# pca10040_sheet3_buttons_and_leds.net
KiCad netlist of a schematic drawn in Altium Designer
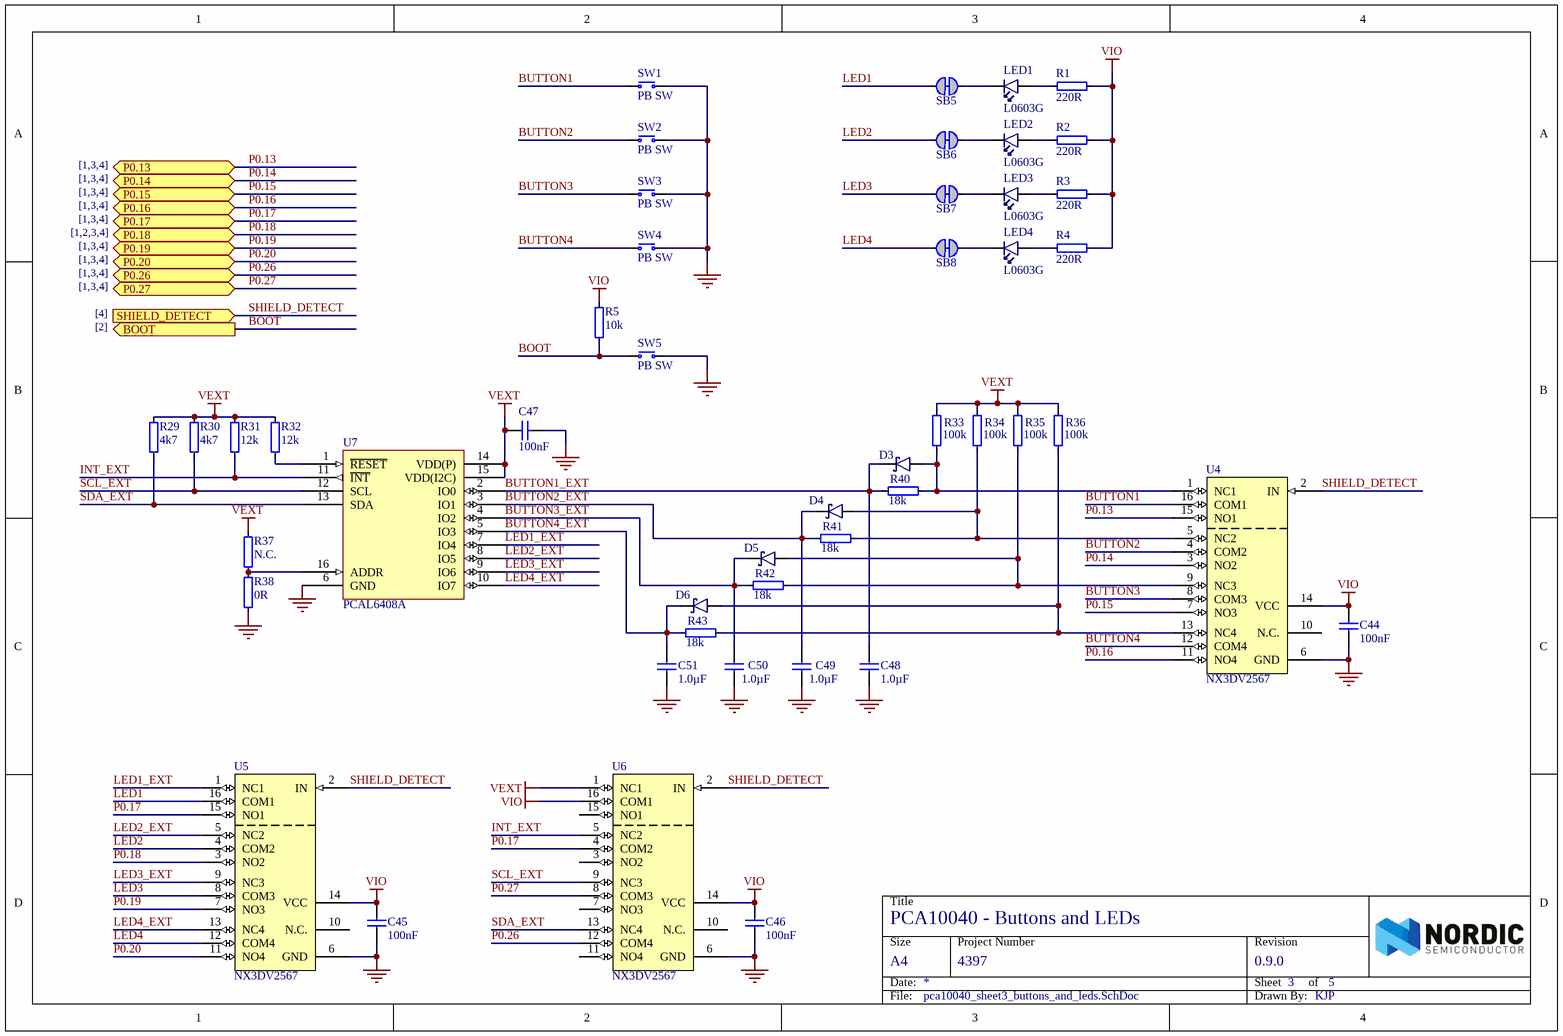
[diagram p0: pca10040_sheet3_buttons_and_leds.SchDoc]

(export (version "E")
  (design (tool "Eeschema 10.0.6"))
  (components
    (comp (ref "C44")
      (value "100nF")
      (footprint "CAPC1005X04L")
      (description "Capacitor, X7R, ±10%")
      (fields (field (name "PART NUMBER") "C0402-100n") (field (name "PUBLISHER") "Nordic Semiconductor"))
      (libsource (lib "Nordic Passive DB") (part "CAP"))
    )
    (comp (ref "C45")
      (value "100nF")
      (footprint "CAPC1005X04L")
      (description "Capacitor, X7R, ±10%")
      (fields (field (name "PART NUMBER") "C0402-100n") (field (name "PUBLISHER") "Nordic Semiconductor"))
      (libsource (lib "Nordic Passive DB") (part "CAP"))
    )
    (comp (ref "C46")
      (value "100nF")
      (footprint "CAPC1005X04L")
      (description "Capacitor, X7R, ±10%")
      (fields (field (name "PART NUMBER") "C0402-100n") (field (name "PUBLISHER") "Nordic Semiconductor"))
      (libsource (lib "Nordic Passive DB") (part "CAP"))
    )
    (comp (ref "C47")
      (value "100nF")
      (footprint "CAPC1005X04L")
      (description "Capacitor, X7R, ±10%")
      (fields (field (name "PART NUMBER") "C0402-100n") (field (name "PUBLISHER") "Nordic Semiconductor"))
      (libsource (lib "Nordic Passive DB") (part "CAP"))
    )
    (comp (ref "C48")
      (value "1.0µF")
      (footprint "CAPC1005X04L")
      (description "Capacitor, X5R, ±5%")
      (fields (field (name "PART NUMBER") "C0402-1µ0") (field (name "PUBLISHER") "Nordic Semiconductor"))
      (libsource (lib "Nordic Passive DB") (part "CAP"))
    )
    (comp (ref "C49")
      (value "1.0µF")
      (footprint "CAPC1005X04L")
      (description "Capacitor, X5R, ±5%")
      (fields (field (name "PART NUMBER") "C0402-1µ0") (field (name "PUBLISHER") "Nordic Semiconductor"))
      (libsource (lib "Nordic Passive DB") (part "CAP"))
    )
    (comp (ref "C50")
      (value "1.0µF")
      (footprint "CAPC1005X04L")
      (description "Capacitor, X5R, ±5%")
      (fields (field (name "PART NUMBER") "C0402-1µ0") (field (name "PUBLISHER") "Nordic Semiconductor"))
      (libsource (lib "Nordic Passive DB") (part "CAP"))
    )
    (comp (ref "C51")
      (value "1.0µF")
      (footprint "CAPC1005X04L")
      (description "Capacitor, X5R, ±5%")
      (fields (field (name "PART NUMBER") "C0402-1µ0") (field (name "PUBLISHER") "Nordic Semiconductor"))
      (libsource (lib "Nordic Passive DB") (part "CAP"))
    )
    (comp (ref "D3")
      (value "1PS79SB30.115")
      (footprint "SOD-523")
      (description "Diode Schottky Vf=0.38, Vr=40V, If=200mA, Ir=500nA")
      (fields (field (name "MANUFACTURER") "NXP") (field (name "PUBLISHER") "Nordic Semiconductor"))
      (libsource (lib "Nordic Discrete DB") (part "D{colon}SCHOTTKY"))
    )
    (comp (ref "D4")
      (value "1PS79SB30.115")
      (footprint "SOD-523")
      (description "Diode Schottky Vf=0.38, Vr=40V, If=200mA, Ir=500nA")
      (fields (field (name "MANUFACTURER") "NXP") (field (name "PUBLISHER") "Nordic Semiconductor"))
      (libsource (lib "Nordic Discrete DB") (part "D{colon}SCHOTTKY"))
    )
    (comp (ref "D5")
      (value "1PS79SB30.115")
      (footprint "SOD-523")
      (description "Diode Schottky Vf=0.38, Vr=40V, If=200mA, Ir=500nA")
      (fields (field (name "MANUFACTURER") "NXP") (field (name "PUBLISHER") "Nordic Semiconductor"))
      (libsource (lib "Nordic Discrete DB") (part "D{colon}SCHOTTKY"))
    )
    (comp (ref "D6")
      (value "1PS79SB30.115")
      (footprint "SOD-523")
      (description "Diode Schottky Vf=0.38, Vr=40V, If=200mA, Ir=500nA")
      (fields (field (name "MANUFACTURER") "NXP") (field (name "PUBLISHER") "Nordic Semiconductor"))
      (libsource (lib "Nordic Discrete DB") (part "D{colon}SCHOTTKY"))
    )
    (comp (ref "LED1")
      (value "L0603G")
      (footprint "LED_0603_G")
      (description "LED 0603, EL19-21SYGC")
      (fields
        (field (name "PART NUMBER") "EL19-21SYGC")
        (field (name "MANUFACTURER") "Everlight")
        (field (name "PUBLISHER") "Nordic Semiconductor")
      )
      (libsource (lib "Nordic Discrete DB") (part "D{colon}LED"))
    )
    (comp (ref "LED2")
      (value "L0603G")
      (footprint "LED_0603_G")
      (description "LED 0603, EL19-21SYGC")
      (fields
        (field (name "PART NUMBER") "EL19-21SYGC")
        (field (name "MANUFACTURER") "Everlight")
        (field (name "PUBLISHER") "Nordic Semiconductor")
      )
      (libsource (lib "Nordic Discrete DB") (part "D{colon}LED"))
    )
    (comp (ref "LED3")
      (value "L0603G")
      (footprint "LED_0603_G")
      (description "LED 0603, EL19-21SYGC")
      (fields
        (field (name "PART NUMBER") "EL19-21SYGC")
        (field (name "MANUFACTURER") "Everlight")
        (field (name "PUBLISHER") "Nordic Semiconductor")
      )
      (libsource (lib "Nordic Discrete DB") (part "D{colon}LED"))
    )
    (comp (ref "LED4")
      (value "L0603G")
      (footprint "LED_0603_G")
      (description "LED 0603, EL19-21SYGC")
      (fields
        (field (name "PART NUMBER") "EL19-21SYGC")
        (field (name "MANUFACTURER") "Everlight")
        (field (name "PUBLISHER") "Nordic Semiconductor")
      )
      (libsource (lib "Nordic Discrete DB") (part "D{colon}LED"))
    )
    (comp (ref "R1")
      (value "220R")
      (footprint "RESC1005X04L")
      (description "Resistor, ±1%, 0.063W")
      (fields (field (name "PART NUMBER") "R0402-220") (field (name "PUBLISHER") "Nordic Semiconductor"))
      (libsource (lib "Nordic Passive DB") (part "RES_1"))
    )
    (comp (ref "R2")
      (value "220R")
      (footprint "RESC1005X04L")
      (description "Resistor, ±1%, 0.063W")
      (fields (field (name "PART NUMBER") "R0402-220") (field (name "PUBLISHER") "Nordic Semiconductor"))
      (libsource (lib "Nordic Passive DB") (part "RES_1"))
    )
    (comp (ref "R3")
      (value "220R")
      (footprint "RESC1005X04L")
      (description "Resistor, ±1%, 0.063W")
      (fields (field (name "PART NUMBER") "R0402-220") (field (name "PUBLISHER") "Nordic Semiconductor"))
      (libsource (lib "Nordic Passive DB") (part "RES_1"))
    )
    (comp (ref "R4")
      (value "220R")
      (footprint "RESC1005X04L")
      (description "Resistor, ±1%, 0.063W")
      (fields (field (name "PART NUMBER") "R0402-220") (field (name "PUBLISHER") "Nordic Semiconductor"))
      (libsource (lib "Nordic Passive DB") (part "RES_1"))
    )
    (comp (ref "R5")
      (value "10k")
      (footprint "RESC1005X04L")
      (description "Resistor, ±1%, 0.063W")
      (fields (field (name "PART NUMBER") "R0402-10k") (field (name "PUBLISHER") "Nordic Semiconductor"))
      (libsource (lib "Nordic Passive DB") (part "RES_1"))
    )
    (comp (ref "R29")
      (value "4k7")
      (footprint "RESC1005X04L")
      (description "Resistor, ±1%, 0.063W")
      (fields (field (name "PART NUMBER") "R0402-4k7") (field (name "PUBLISHER") "Nordic Semiconductor"))
      (libsource (lib "Nordic Passive DB") (part "RES_1"))
    )
    (comp (ref "R30")
      (value "4k7")
      (footprint "RESC1005X04L")
      (description "Resistor, ±1%, 0.063W")
      (fields (field (name "PART NUMBER") "R0402-4k7") (field (name "PUBLISHER") "Nordic Semiconductor"))
      (libsource (lib "Nordic Passive DB") (part "RES_1"))
    )
    (comp (ref "R31")
      (value "12k")
      (footprint "RESC1005X04L")
      (description "Resistor, ±1%, 0.063W")
      (fields (field (name "PART NUMBER") "R0402-12k") (field (name "PUBLISHER") "Nordic Semiconductor"))
      (libsource (lib "Nordic Passive DB") (part "RES_1"))
    )
    (comp (ref "R32")
      (value "12k")
      (footprint "RESC1005X04L")
      (description "Resistor, ±1%, 0.063W")
      (fields (field (name "PART NUMBER") "R0402-12k") (field (name "PUBLISHER") "Nordic Semiconductor"))
      (libsource (lib "Nordic Passive DB") (part "RES_1"))
    )
    (comp (ref "R33")
      (value "100k")
      (footprint "RESC1005X04L")
      (description "Resistor, ±1%, 0.063W")
      (fields (field (name "PART NUMBER") "R0402-100k") (field (name "PUBLISHER") "Nordic Semiconductor"))
      (libsource (lib "Nordic Passive DB") (part "RES_1"))
    )
    (comp (ref "R34")
      (value "100k")
      (footprint "RESC1005X04L")
      (description "Resistor, ±1%, 0.063W")
      (fields (field (name "PART NUMBER") "R0402-100k") (field (name "PUBLISHER") "Nordic Semiconductor"))
      (libsource (lib "Nordic Passive DB") (part "RES_1"))
    )
    (comp (ref "R35")
      (value "100k")
      (footprint "RESC1005X04L")
      (description "Resistor, ±1%, 0.063W")
      (fields (field (name "PART NUMBER") "R0402-100k") (field (name "PUBLISHER") "Nordic Semiconductor"))
      (libsource (lib "Nordic Passive DB") (part "RES_1"))
    )
    (comp (ref "R36")
      (value "100k")
      (footprint "RESC1005X04L")
      (description "Resistor, ±1%, 0.063W")
      (fields (field (name "PART NUMBER") "R0402-100k") (field (name "PUBLISHER") "Nordic Semiconductor"))
      (libsource (lib "Nordic Passive DB") (part "RES_1"))
    )
    (comp (ref "R37")
      (value "N.C.")
      (footprint "RESC1005X04L")
      (description "Not mounted")
      (fields (field (name "PART NUMBER") "R0402-N.C.") (field (name "PUBLISHER") "Nordic Semiconductor"))
      (libsource (lib "Nordic Passive DB") (part "RES_1"))
    )
    (comp (ref "R38")
      (value "0R")
      (footprint "RESC1005X04L")
      (description "Resistor, ±5%, 0.063W")
      (fields (field (name "PART NUMBER") "R0402-0R") (field (name "PUBLISHER") "Nordic Semiconductor"))
      (libsource (lib "Nordic Passive DB") (part "RES_1"))
    )
    (comp (ref "R40")
      (value "18k")
      (footprint "RESC1005X04L")
      (description "Resistor, ±1%, 0.063W")
      (fields (field (name "PART NUMBER") "R0402-18k") (field (name "PUBLISHER") "Nordic Semiconductor"))
      (libsource (lib "Nordic Passive DB") (part "RES_1"))
    )
    (comp (ref "R41")
      (value "18k")
      (footprint "RESC1005X04L")
      (description "Resistor, ±1%, 0.063W")
      (fields (field (name "PART NUMBER") "R0402-18k") (field (name "PUBLISHER") "Nordic Semiconductor"))
      (libsource (lib "Nordic Passive DB") (part "RES_1"))
    )
    (comp (ref "R42")
      (value "18k")
      (footprint "RESC1005X04L")
      (description "Resistor, ±1%, 0.063W")
      (fields (field (name "PART NUMBER") "R0402-18k") (field (name "PUBLISHER") "Nordic Semiconductor"))
      (libsource (lib "Nordic Passive DB") (part "RES_1"))
    )
    (comp (ref "R43")
      (value "18k")
      (footprint "RESC1005X04L")
      (description "Resistor, ±1%, 0.063W")
      (fields (field (name "PART NUMBER") "R0402-18k") (field (name "PUBLISHER") "Nordic Semiconductor"))
      (libsource (lib "Nordic Passive DB") (part "RES_1"))
    )
    (comp (ref "SB5")
      (value "Solderbridge")
      (footprint "Solderbridge_Shorted")
      (description "Shorted Solderbridge")
      (fields
        (field (name "PART NUMBER") "Solderbridge Shorted")
        (field (name "PUBLISHER") "Nordic Semiconductor")
      )
      (libsource (lib "Nordic Passive DB") (part "SOLDERBRIDGE_SHORTED"))
    )
    (comp (ref "SB6")
      (value "Solderbridge")
      (footprint "Solderbridge_Shorted")
      (description "Shorted Solderbridge")
      (fields
        (field (name "PART NUMBER") "Solderbridge Shorted")
        (field (name "PUBLISHER") "Nordic Semiconductor")
      )
      (libsource (lib "Nordic Passive DB") (part "SOLDERBRIDGE_SHORTED"))
    )
    (comp (ref "SB7")
      (value "Solderbridge")
      (footprint "Solderbridge_Shorted")
      (description "Shorted Solderbridge")
      (fields
        (field (name "PART NUMBER") "Solderbridge Shorted")
        (field (name "PUBLISHER") "Nordic Semiconductor")
      )
      (libsource (lib "Nordic Passive DB") (part "SOLDERBRIDGE_SHORTED"))
    )
    (comp (ref "SB8")
      (value "Solderbridge")
      (footprint "Solderbridge_Shorted")
      (description "Shorted Solderbridge")
      (fields
        (field (name "PART NUMBER") "Solderbridge Shorted")
        (field (name "PUBLISHER") "Nordic Semiconductor")
      )
      (libsource (lib "Nordic Passive DB") (part "SOLDERBRIDGE_SHORTED"))
    )
    (comp (ref "SW1")
      (value "PB SW")
      (footprint "ALPS_SKHUxxx010_WO_GND")
      (description "ALPS - SKHUALE010 - Tactile Switch, SPNO, SMD, 6.5x6.2x2.5mm")
      (fields
        (field (name "PART NUMBER") "ALPS_SKHUALE010")
        (field (name "MANUFACTURER") "Alps")
        (field (name "PUBLISHER") "Nordic Semiconductor")
      )
      (libsource (lib "Nordic Discrete DB") (part "SW-PB"))
    )
    (comp (ref "SW2")
      (value "PB SW")
      (footprint "ALPS_SKHUxxx010_WO_GND")
      (description "ALPS - SKHUALE010 - Tactile Switch, SPNO, SMD, 6.5x6.2x2.5mm")
      (fields
        (field (name "PART NUMBER") "ALPS_SKHUALE010")
        (field (name "MANUFACTURER") "Alps")
        (field (name "PUBLISHER") "Nordic Semiconductor")
      )
      (libsource (lib "Nordic Discrete DB") (part "SW-PB"))
    )
    (comp (ref "SW3")
      (value "PB SW")
      (footprint "ALPS_SKHUxxx010_WO_GND")
      (description "ALPS - SKHUALE010 - Tactile Switch, SPNO, SMD, 6.5x6.2x2.5mm")
      (fields
        (field (name "PART NUMBER") "ALPS_SKHUALE010")
        (field (name "MANUFACTURER") "Alps")
        (field (name "PUBLISHER") "Nordic Semiconductor")
      )
      (libsource (lib "Nordic Discrete DB") (part "SW-PB"))
    )
    (comp (ref "SW4")
      (value "PB SW")
      (footprint "ALPS_SKHUxxx010_WO_GND")
      (description "ALPS - SKHUALE010 - Tactile Switch, SPNO, SMD, 6.5x6.2x2.5mm")
      (fields
        (field (name "PART NUMBER") "ALPS_SKHUALE010")
        (field (name "MANUFACTURER") "Alps")
        (field (name "PUBLISHER") "Nordic Semiconductor")
      )
      (libsource (lib "Nordic Discrete DB") (part "SW-PB"))
    )
    (comp (ref "SW5")
      (value "PB SW")
      (footprint "ALPS_SKHUxxx010_WO_GND")
      (description "ALPS - SKHUALE010 - Tactile Switch, SPNO, SMD, 6.5x6.2x2.5mm")
      (fields
        (field (name "PART NUMBER") "ALPS_SKHUALE010")
        (field (name "MANUFACTURER") "Alps")
        (field (name "PUBLISHER") "Nordic Semiconductor")
      )
      (libsource (lib "Nordic Discrete DB") (part "SW-PB"))
    )
    (comp (ref "U4")
      (value "NX3DV2567")
      (footprint "XQFN40P180X260X50-16N")
      (description "Low-ohmic four-pole double-throw analog switch")
      (fields
        (field (name "PART NUMBER") "NX3DV2567GU")
        (field (name "MANUFACTURER") "NXP Semiconductors")
        (field (name "PUBLISHER") "Nordic Semiconductor")
      )
      (libsource (lib "Nordic Active DB") (part "NX3DV2567"))
    )
    (comp (ref "U5")
      (value "NX3DV2567")
      (footprint "XQFN40P180X260X50-16N")
      (description "Low-ohmic four-pole double-throw analog switch")
      (fields
        (field (name "PART NUMBER") "NX3DV2567GU")
        (field (name "MANUFACTURER") "NXP Semiconductors")
        (field (name "PUBLISHER") "Nordic Semiconductor")
      )
      (libsource (lib "Nordic Active DB") (part "NX3DV2567"))
    )
    (comp (ref "U6")
      (value "NX3DV2567")
      (footprint "XQFN40P180X260X50-16N")
      (description "Low-ohmic four-pole double-throw analog switch")
      (fields
        (field (name "PART NUMBER") "NX3DV2567GU")
        (field (name "MANUFACTURER") "NXP Semiconductors")
        (field (name "PUBLISHER") "Nordic Semiconductor")
      )
      (libsource (lib "Nordic Active DB") (part "NX3DV2567"))
    )
    (comp (ref "U7")
      (value "PCAL6408A")
      (footprint "XQFN40P180X260X50-16N")
      (description "8-bit I2C-bus I/O expander with interrupt output")
      (fields
        (field (name "PART NUMBER") "PCAL6408AHK")
        (field (name "MANUFACTURER") "NXP Semiconductors")
        (field (name "PUBLISHER") "Nordic Semiconductor")
      )
      (libsource (lib "Nordic Active DB") (part "PCAL6408AHK"))
    )
  )
  (nets
    (net (code "1") (name "/BOOT") (class "Default")
      (node (ref "R5") (pin "1") (pinfunction "1_1") (pintype "passive"))
      (node (ref "SW5") (pin "1") (pinfunction "N.O_1") (pintype "passive"))
    )
    (net (code "2") (name "/BUTTON1") (class "Default")
      (node (ref "SW1") (pin "1") (pinfunction "N.O_1") (pintype "passive"))
      (node (ref "U4") (pin "16") (pinfunction "COM1_16") (pintype "bidirectional"))
    )
    (net (code "3") (name "/BUTTON1_EXT") (class "Default")
      (node (ref "C48") (pin "1") (pinfunction "1_1") (pintype "passive"))
      (node (ref "D3") (pin "3") (pinfunction "C_3") (pintype "passive"))
      (node (ref "R40") (pin "1") (pinfunction "1_1") (pintype "passive"))
      (node (ref "U7") (pin "2") (pinfunction "IO0_2") (pintype "bidirectional"))
    )
    (net (code "4") (name "/BUTTON2") (class "Default")
      (node (ref "SW2") (pin "1") (pinfunction "N.O_1") (pintype "passive"))
      (node (ref "U4") (pin "4") (pinfunction "COM2_4") (pintype "bidirectional"))
    )
    (net (code "5") (name "/BUTTON2_EXT") (class "Default")
      (node (ref "C49") (pin "2") (pinfunction "2_2") (pintype "passive"))
      (node (ref "D4") (pin "3") (pinfunction "C_3") (pintype "passive"))
      (node (ref "R41") (pin "1") (pinfunction "1_1") (pintype "passive"))
      (node (ref "U7") (pin "3") (pinfunction "IO1_3") (pintype "bidirectional"))
    )
    (net (code "6") (name "/BUTTON3") (class "Default")
      (node (ref "SW3") (pin "1") (pinfunction "N.O_1") (pintype "passive"))
      (node (ref "U4") (pin "8") (pinfunction "COM3_8") (pintype "bidirectional"))
    )
    (net (code "7") (name "/BUTTON3_EXT") (class "Default")
      (node (ref "C50") (pin "2") (pinfunction "2_2") (pintype "passive"))
      (node (ref "D5") (pin "3") (pinfunction "C_3") (pintype "passive"))
      (node (ref "R42") (pin "1") (pinfunction "1_1") (pintype "passive"))
      (node (ref "U7") (pin "4") (pinfunction "IO2_4") (pintype "bidirectional"))
    )
    (net (code "8") (name "/BUTTON4") (class "Default")
      (node (ref "SW4") (pin "1") (pinfunction "N.O_1") (pintype "passive"))
      (node (ref "U4") (pin "12") (pinfunction "COM4_12") (pintype "bidirectional"))
    )
    (net (code "9") (name "/BUTTON4_EXT") (class "Default")
      (node (ref "C51") (pin "1") (pinfunction "1_1") (pintype "passive"))
      (node (ref "D6") (pin "3") (pinfunction "C_3") (pintype "passive"))
      (node (ref "R43") (pin "1") (pinfunction "1_1") (pintype "passive"))
      (node (ref "U7") (pin "5") (pinfunction "IO3_5") (pintype "bidirectional"))
    )
    (net (code "10") (name "/INT_EXT") (class "Default")
      (node (ref "R31") (pin "1") (pinfunction "1_1") (pintype "passive"))
      (node (ref "U6") (pin "5") (pinfunction "NC2_5") (pintype "bidirectional"))
      (node (ref "U7") (pin "11") (pinfunction "~{INT}_11") (pintype "output"))
    )
    (net (code "11") (name "/LED1") (class "Default")
      (node (ref "SB5") (pin "1") (pinfunction "0_1") (pintype "passive"))
      (node (ref "U5") (pin "16") (pinfunction "COM1_16") (pintype "bidirectional"))
    )
    (net (code "12") (name "/LED1_EXT") (class "Default")
      (node (ref "U5") (pin "1") (pinfunction "NC1_1") (pintype "bidirectional"))
      (node (ref "U7") (pin "7") (pinfunction "IO4_7") (pintype "bidirectional"))
    )
    (net (code "13") (name "/LED2") (class "Default")
      (node (ref "SB6") (pin "1") (pinfunction "0_1") (pintype "passive"))
      (node (ref "U5") (pin "4") (pinfunction "COM2_4") (pintype "bidirectional"))
    )
    (net (code "14") (name "/LED2_EXT") (class "Default")
      (node (ref "U5") (pin "5") (pinfunction "NC2_5") (pintype "bidirectional"))
      (node (ref "U7") (pin "8") (pinfunction "IO5_8") (pintype "bidirectional"))
    )
    (net (code "15") (name "/LED3") (class "Default")
      (node (ref "SB7") (pin "1") (pinfunction "0_1") (pintype "passive"))
      (node (ref "U5") (pin "8") (pinfunction "COM3_8") (pintype "bidirectional"))
    )
    (net (code "16") (name "/LED3_EXT") (class "Default")
      (node (ref "U5") (pin "9") (pinfunction "NC3_9") (pintype "bidirectional"))
      (node (ref "U7") (pin "9") (pinfunction "IO6_9") (pintype "bidirectional"))
    )
    (net (code "17") (name "/LED4") (class "Default")
      (node (ref "SB8") (pin "1") (pinfunction "0_1") (pintype "passive"))
      (node (ref "U5") (pin "12") (pinfunction "COM4_12") (pintype "bidirectional"))
    )
    (net (code "18") (name "/LED4_EXT") (class "Default")
      (node (ref "U5") (pin "13") (pinfunction "NC4_13") (pintype "bidirectional"))
      (node (ref "U7") (pin "10") (pinfunction "IO7_10") (pintype "bidirectional"))
    )
    (net (code "19") (name "/P0.13") (class "Default")
      (node (ref "U4") (pin "15") (pinfunction "NO1_15") (pintype "bidirectional"))
    )
    (net (code "20") (name "/P0.14") (class "Default")
      (node (ref "U4") (pin "3") (pinfunction "NO2_3") (pintype "bidirectional"))
    )
    (net (code "21") (name "/P0.15") (class "Default")
      (node (ref "U4") (pin "7") (pinfunction "NO3_7") (pintype "bidirectional"))
    )
    (net (code "22") (name "/P0.16") (class "Default")
      (node (ref "U4") (pin "11") (pinfunction "NO4_11") (pintype "bidirectional"))
    )
    (net (code "23") (name "/P0.17") (class "Default")
      (node (ref "U5") (pin "15") (pinfunction "NO1_15") (pintype "bidirectional"))
      (node (ref "U6") (pin "4") (pinfunction "COM2_4") (pintype "bidirectional"))
    )
    (net (code "24") (name "/P0.18") (class "Default")
      (node (ref "U5") (pin "3") (pinfunction "NO2_3") (pintype "bidirectional"))
    )
    (net (code "25") (name "/P0.19") (class "Default")
      (node (ref "U5") (pin "7") (pinfunction "NO3_7") (pintype "bidirectional"))
    )
    (net (code "26") (name "/P0.20") (class "Default")
      (node (ref "U5") (pin "11") (pinfunction "NO4_11") (pintype "bidirectional"))
    )
    (net (code "27") (name "/P0.26") (class "Default")
      (node (ref "U6") (pin "12") (pinfunction "COM4_12") (pintype "bidirectional"))
    )
    (net (code "28") (name "/P0.27") (class "Default")
      (node (ref "U6") (pin "8") (pinfunction "COM3_8") (pintype "bidirectional"))
    )
    (net (code "29") (name "/SCL_EXT") (class "Default")
      (node (ref "R30") (pin "1") (pinfunction "1_1") (pintype "passive"))
      (node (ref "U6") (pin "9") (pinfunction "NC3_9") (pintype "bidirectional"))
      (node (ref "U7") (pin "12") (pinfunction "SCL_12") (pintype "power_in"))
    )
    (net (code "30") (name "/SDA_EXT") (class "Default")
      (node (ref "R29") (pin "1") (pinfunction "1_1") (pintype "passive"))
      (node (ref "U6") (pin "13") (pinfunction "NC4_13") (pintype "bidirectional"))
      (node (ref "U7") (pin "13") (pinfunction "SDA_13") (pintype "passive"))
    )
    (net (code "31") (name "/SHIELD_DETECT") (class "Default")
      (node (ref "U4") (pin "2") (pinfunction "IN_2") (pintype "input"))
      (node (ref "U5") (pin "2") (pinfunction "IN_2") (pintype "input"))
      (node (ref "U6") (pin "2") (pinfunction "IN_2") (pintype "input"))
    )
    (net (code "32") (name "GND") (class "Default")
      (node (ref "C44") (pin "1") (pinfunction "1_1") (pintype "passive"))
      (node (ref "C45") (pin "1") (pinfunction "1_1") (pintype "passive"))
      (node (ref "C46") (pin "1") (pinfunction "1_1") (pintype "passive"))
      (node (ref "C47") (pin "1") (pinfunction "1_1") (pintype "passive"))
      (node (ref "C48") (pin "2") (pinfunction "2_2") (pintype "passive"))
      (node (ref "C49") (pin "1") (pinfunction "1_1") (pintype "passive"))
      (node (ref "C50") (pin "1") (pinfunction "1_1") (pintype "passive"))
      (node (ref "C51") (pin "2") (pinfunction "2_2") (pintype "passive"))
      (node (ref "R38") (pin "1") (pinfunction "1_1") (pintype "passive"))
      (node (ref "SW1") (pin "2") (pinfunction "COM_2") (pintype "passive"))
      (node (ref "SW2") (pin "2") (pinfunction "COM_2") (pintype "passive"))
      (node (ref "SW3") (pin "2") (pinfunction "COM_2") (pintype "passive"))
      (node (ref "SW4") (pin "2") (pinfunction "COM_2") (pintype "passive"))
      (node (ref "SW5") (pin "2") (pinfunction "COM_2") (pintype "passive"))
      (node (ref "U4") (pin "6") (pinfunction "GND_6") (pintype "power_in"))
      (node (ref "U5") (pin "6") (pinfunction "GND_6") (pintype "power_in"))
      (node (ref "U6") (pin "6") (pinfunction "GND_6") (pintype "power_in"))
      (node (ref "U7") (pin "6") (pinfunction "GND_6") (pintype "power_in"))
    )
    (net (code "33") (name "Net-(D3-A)") (class "Default")
      (node (ref "D3") (pin "1") (pinfunction "A_1") (pintype "passive"))
      (node (ref "R33") (pin "1") (pinfunction "1_1") (pintype "passive"))
      (node (ref "R40") (pin "2") (pinfunction "2_2") (pintype "passive"))
      (node (ref "U4") (pin "1") (pinfunction "NC1_1") (pintype "bidirectional"))
    )
    (net (code "34") (name "Net-(D4-A)") (class "Default")
      (node (ref "D4") (pin "1") (pinfunction "A_1") (pintype "passive"))
      (node (ref "R34") (pin "1") (pinfunction "1_1") (pintype "passive"))
      (node (ref "R41") (pin "2") (pinfunction "2_2") (pintype "passive"))
      (node (ref "U4") (pin "5") (pinfunction "NC2_5") (pintype "bidirectional"))
    )
    (net (code "35") (name "Net-(D5-A)") (class "Default")
      (node (ref "D5") (pin "1") (pinfunction "A_1") (pintype "passive"))
      (node (ref "R35") (pin "1") (pinfunction "1_1") (pintype "passive"))
      (node (ref "R42") (pin "2") (pinfunction "2_2") (pintype "passive"))
      (node (ref "U4") (pin "9") (pinfunction "NC3_9") (pintype "bidirectional"))
    )
    (net (code "36") (name "Net-(D6-A)") (class "Default")
      (node (ref "D6") (pin "1") (pinfunction "A_1") (pintype "passive"))
      (node (ref "R36") (pin "1") (pinfunction "1_1") (pintype "passive"))
      (node (ref "R43") (pin "2") (pinfunction "2_2") (pintype "passive"))
      (node (ref "U4") (pin "13") (pinfunction "NC4_13") (pintype "bidirectional"))
    )
    (net (code "37") (name "Net-(LED1-A)") (class "Default")
      (node (ref "LED1") (pin "2") (pinfunction "A_2") (pintype "passive"))
      (node (ref "R1") (pin "1") (pinfunction "1_1") (pintype "passive"))
    )
    (net (code "38") (name "Net-(LED1-C)") (class "Default")
      (node (ref "LED1") (pin "1") (pinfunction "C_1") (pintype "passive"))
      (node (ref "SB5") (pin "2") (pinfunction "1_2") (pintype "passive"))
    )
    (net (code "39") (name "Net-(LED2-A)") (class "Default")
      (node (ref "LED2") (pin "2") (pinfunction "A_2") (pintype "passive"))
      (node (ref "R2") (pin "1") (pinfunction "1_1") (pintype "passive"))
    )
    (net (code "40") (name "Net-(LED2-C)") (class "Default")
      (node (ref "LED2") (pin "1") (pinfunction "C_1") (pintype "passive"))
      (node (ref "SB6") (pin "2") (pinfunction "1_2") (pintype "passive"))
    )
    (net (code "41") (name "Net-(LED3-A)") (class "Default")
      (node (ref "LED3") (pin "2") (pinfunction "A_2") (pintype "passive"))
      (node (ref "R3") (pin "1") (pinfunction "1_1") (pintype "passive"))
    )
    (net (code "42") (name "Net-(LED3-C)") (class "Default")
      (node (ref "LED3") (pin "1") (pinfunction "C_1") (pintype "passive"))
      (node (ref "SB7") (pin "2") (pinfunction "1_2") (pintype "passive"))
    )
    (net (code "43") (name "Net-(LED4-A)") (class "Default")
      (node (ref "LED4") (pin "2") (pinfunction "A_2") (pintype "passive"))
      (node (ref "R4") (pin "1") (pinfunction "1_1") (pintype "passive"))
    )
    (net (code "44") (name "Net-(LED4-C)") (class "Default")
      (node (ref "LED4") (pin "1") (pinfunction "C_1") (pintype "passive"))
      (node (ref "SB8") (pin "2") (pinfunction "1_2") (pintype "passive"))
    )
    (net (code "45") (name "Net-(U7-ADDR)") (class "Default")
      (node (ref "R37") (pin "1") (pinfunction "1_1") (pintype "passive"))
      (node (ref "R38") (pin "2") (pinfunction "2_2") (pintype "passive"))
      (node (ref "U7") (pin "16") (pinfunction "ADDR_16") (pintype "input"))
    )
    (net (code "46") (name "Net-(U7-~{RESET})") (class "Default")
      (node (ref "R32") (pin "1") (pinfunction "1_1") (pintype "passive"))
      (node (ref "U7") (pin "1") (pinfunction "~{RESET}_1") (pintype "input"))
    )
    (net (code "47") (name "VEXT") (class "Default")
      (node (ref "C47") (pin "2") (pinfunction "2_2") (pintype "passive"))
      (node (ref "R29") (pin "2") (pinfunction "2_2") (pintype "passive"))
      (node (ref "R30") (pin "2") (pinfunction "2_2") (pintype "passive"))
      (node (ref "R31") (pin "2") (pinfunction "2_2") (pintype "passive"))
      (node (ref "R32") (pin "2") (pinfunction "2_2") (pintype "passive"))
      (node (ref "R33") (pin "2") (pinfunction "2_2") (pintype "passive"))
      (node (ref "R34") (pin "2") (pinfunction "2_2") (pintype "passive"))
      (node (ref "R35") (pin "2") (pinfunction "2_2") (pintype "passive"))
      (node (ref "R36") (pin "2") (pinfunction "2_2") (pintype "passive"))
      (node (ref "R37") (pin "2") (pinfunction "2_2") (pintype "passive"))
      (node (ref "U6") (pin "1") (pinfunction "NC1_1") (pintype "bidirectional"))
      (node (ref "U7") (pin "14") (pinfunction "VDD(P)_14") (pintype "power_in"))
      (node (ref "U7") (pin "15") (pinfunction "VDD(I2C)_15") (pintype "power_in"))
    )
    (net (code "48") (name "VIO") (class "Default")
      (node (ref "C44") (pin "2") (pinfunction "2_2") (pintype "passive"))
      (node (ref "C45") (pin "2") (pinfunction "2_2") (pintype "passive"))
      (node (ref "C46") (pin "2") (pinfunction "2_2") (pintype "passive"))
      (node (ref "R1") (pin "2") (pinfunction "2_2") (pintype "passive"))
      (node (ref "R2") (pin "2") (pinfunction "2_2") (pintype "passive"))
      (node (ref "R3") (pin "2") (pinfunction "2_2") (pintype "passive"))
      (node (ref "R4") (pin "2") (pinfunction "2_2") (pintype "passive"))
      (node (ref "R5") (pin "2") (pinfunction "2_2") (pintype "passive"))
      (node (ref "U4") (pin "14") (pinfunction "VCC_14") (pintype "power_in"))
      (node (ref "U5") (pin "14") (pinfunction "VCC_14") (pintype "power_in"))
      (node (ref "U6") (pin "14") (pinfunction "VCC_14") (pintype "power_in"))
      (node (ref "U6") (pin "16") (pinfunction "COM1_16") (pintype "bidirectional"))
    )
    (net (code "49") (name "unconnected-(U4-N.C.-Pad10)") (class "Default")
      (node (ref "U4") (pin "10") (pinfunction "N.C._10") (pintype "passive"))
    )
    (net (code "50") (name "unconnected-(U5-N.C.-Pad10)") (class "Default")
      (node (ref "U5") (pin "10") (pinfunction "N.C._10") (pintype "passive"))
    )
    (net (code "51") (name "unconnected-(U6-N.C.-Pad10)") (class "Default")
      (node (ref "U6") (pin "10") (pinfunction "N.C._10") (pintype "passive"))
    )
    (net (code "52") (name "unconnected-(U6-NO1-Pad15)") (class "Default")
      (node (ref "U6") (pin "15") (pinfunction "NO1_15") (pintype "bidirectional"))
    )
    (net (code "53") (name "unconnected-(U6-NO2-Pad3)") (class "Default")
      (node (ref "U6") (pin "3") (pinfunction "NO2_3") (pintype "bidirectional"))
    )
    (net (code "54") (name "unconnected-(U6-NO3-Pad7)") (class "Default")
      (node (ref "U6") (pin "7") (pinfunction "NO3_7") (pintype "bidirectional"))
    )
    (net (code "55") (name "unconnected-(U6-NO4-Pad11)") (class "Default")
      (node (ref "U6") (pin "11") (pinfunction "NO4_11") (pintype "bidirectional"))
    )
  )
)
